# Modulo_Servo.net
KiCad netlist of a schematic drawn in Altium Designer
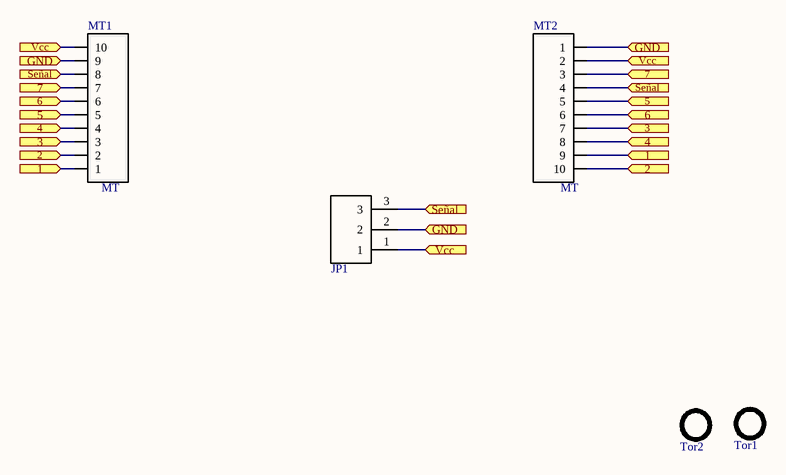
[diagram p0: Modulo Servo.SchDoc]

(export (version "E")
  (design (tool "Eeschema 10.0.6"))
  (components
    (comp (ref "JP1")
      (value "Pines (3X2.54)")
      (footprint "Pin(3X2.54mm)")
      (libsource (lib "Libreria_Borxo_Sch") (part "Pines (3X2.54)"))
    )
    (comp (ref "MT1")
      (value "MT")
      (footprint "Micro-MaTch Famale 1.27mm/SMD")
      (description "Micro-MaTch Famale 1.27mm T/Hole")
      (libsource (lib "") (part "Micro-MaTch Famale 1.27mm_1"))
    )
    (comp (ref "MT2")
      (value "MT")
      (footprint "Micro-MaTch Famale 1.27mm/SMD")
      (description "Micro-MaTch Famale 1.27mm T/Hole")
      (libsource (lib "Libreria_Borxo_Sch") (part "Micro-MaTch Famale 1.27mm"))
    )
    (comp (ref "Tor1")
      (value "Tornillo3MM")
      (footprint "Taladro_3mm")
      (libsource (lib "Libreria_Borxo_Sch") (part "Taladro_3mm"))
    )
    (comp (ref "Tor2")
      (value "Tornillo3MM")
      (footprint "Taladro_3mm")
      (libsource (lib "Libreria_Borxo_Sch") (part "Taladro_3mm"))
    )
  )
  (nets
    (net (code "1") (name "/1") (class "Default")
      (node (ref "MT1") (pin "1") (pinfunction "1_1") (pintype "passive"))
      (node (ref "MT2") (pin "9") (pinfunction "9_9") (pintype "passive"))
    )
    (net (code "2") (name "/2") (class "Default")
      (node (ref "MT1") (pin "2") (pinfunction "2_2") (pintype "passive"))
      (node (ref "MT2") (pin "10") (pinfunction "10_10") (pintype "passive"))
    )
    (net (code "3") (name "/3") (class "Default")
      (node (ref "MT1") (pin "3") (pinfunction "3_3") (pintype "passive"))
      (node (ref "MT2") (pin "7") (pinfunction "7_7") (pintype "passive"))
    )
    (net (code "4") (name "/4") (class "Default")
      (node (ref "MT1") (pin "4") (pinfunction "4_4") (pintype "passive"))
      (node (ref "MT2") (pin "8") (pinfunction "8_8") (pintype "passive"))
    )
    (net (code "5") (name "/5") (class "Default")
      (node (ref "MT1") (pin "5") (pinfunction "5_5") (pintype "passive"))
      (node (ref "MT2") (pin "5") (pinfunction "5_5") (pintype "passive"))
    )
    (net (code "6") (name "/6") (class "Default")
      (node (ref "MT1") (pin "6") (pinfunction "6_6") (pintype "passive"))
      (node (ref "MT2") (pin "6") (pinfunction "6_6") (pintype "passive"))
    )
    (net (code "7") (name "/7") (class "Default")
      (node (ref "MT1") (pin "7") (pinfunction "7_7") (pintype "passive"))
      (node (ref "MT2") (pin "3") (pinfunction "3_3") (pintype "passive"))
    )
    (net (code "8") (name "/GND") (class "Default")
      (node (ref "JP1") (pin "2") (pinfunction "2_2") (pintype "passive"))
      (node (ref "MT1") (pin "9") (pinfunction "9_9") (pintype "passive"))
      (node (ref "MT2") (pin "1") (pinfunction "1_1") (pintype "passive"))
    )
    (net (code "9") (name "/Señal") (class "Default")
      (node (ref "JP1") (pin "3") (pinfunction "3_3") (pintype "passive"))
      (node (ref "MT1") (pin "8") (pinfunction "8_8") (pintype "passive"))
      (node (ref "MT2") (pin "4") (pinfunction "4_4") (pintype "passive"))
    )
    (net (code "10") (name "/Vcc") (class "Default")
      (node (ref "JP1") (pin "1") (pinfunction "1_1") (pintype "passive"))
      (node (ref "MT1") (pin "10") (pinfunction "10_10") (pintype "passive"))
      (node (ref "MT2") (pin "2") (pinfunction "2_2") (pintype "passive"))
    )
  )
)
